# EasyEDA_single_chanel_pump.net
KiCad netlist of a schematic drawn in EasyEDA
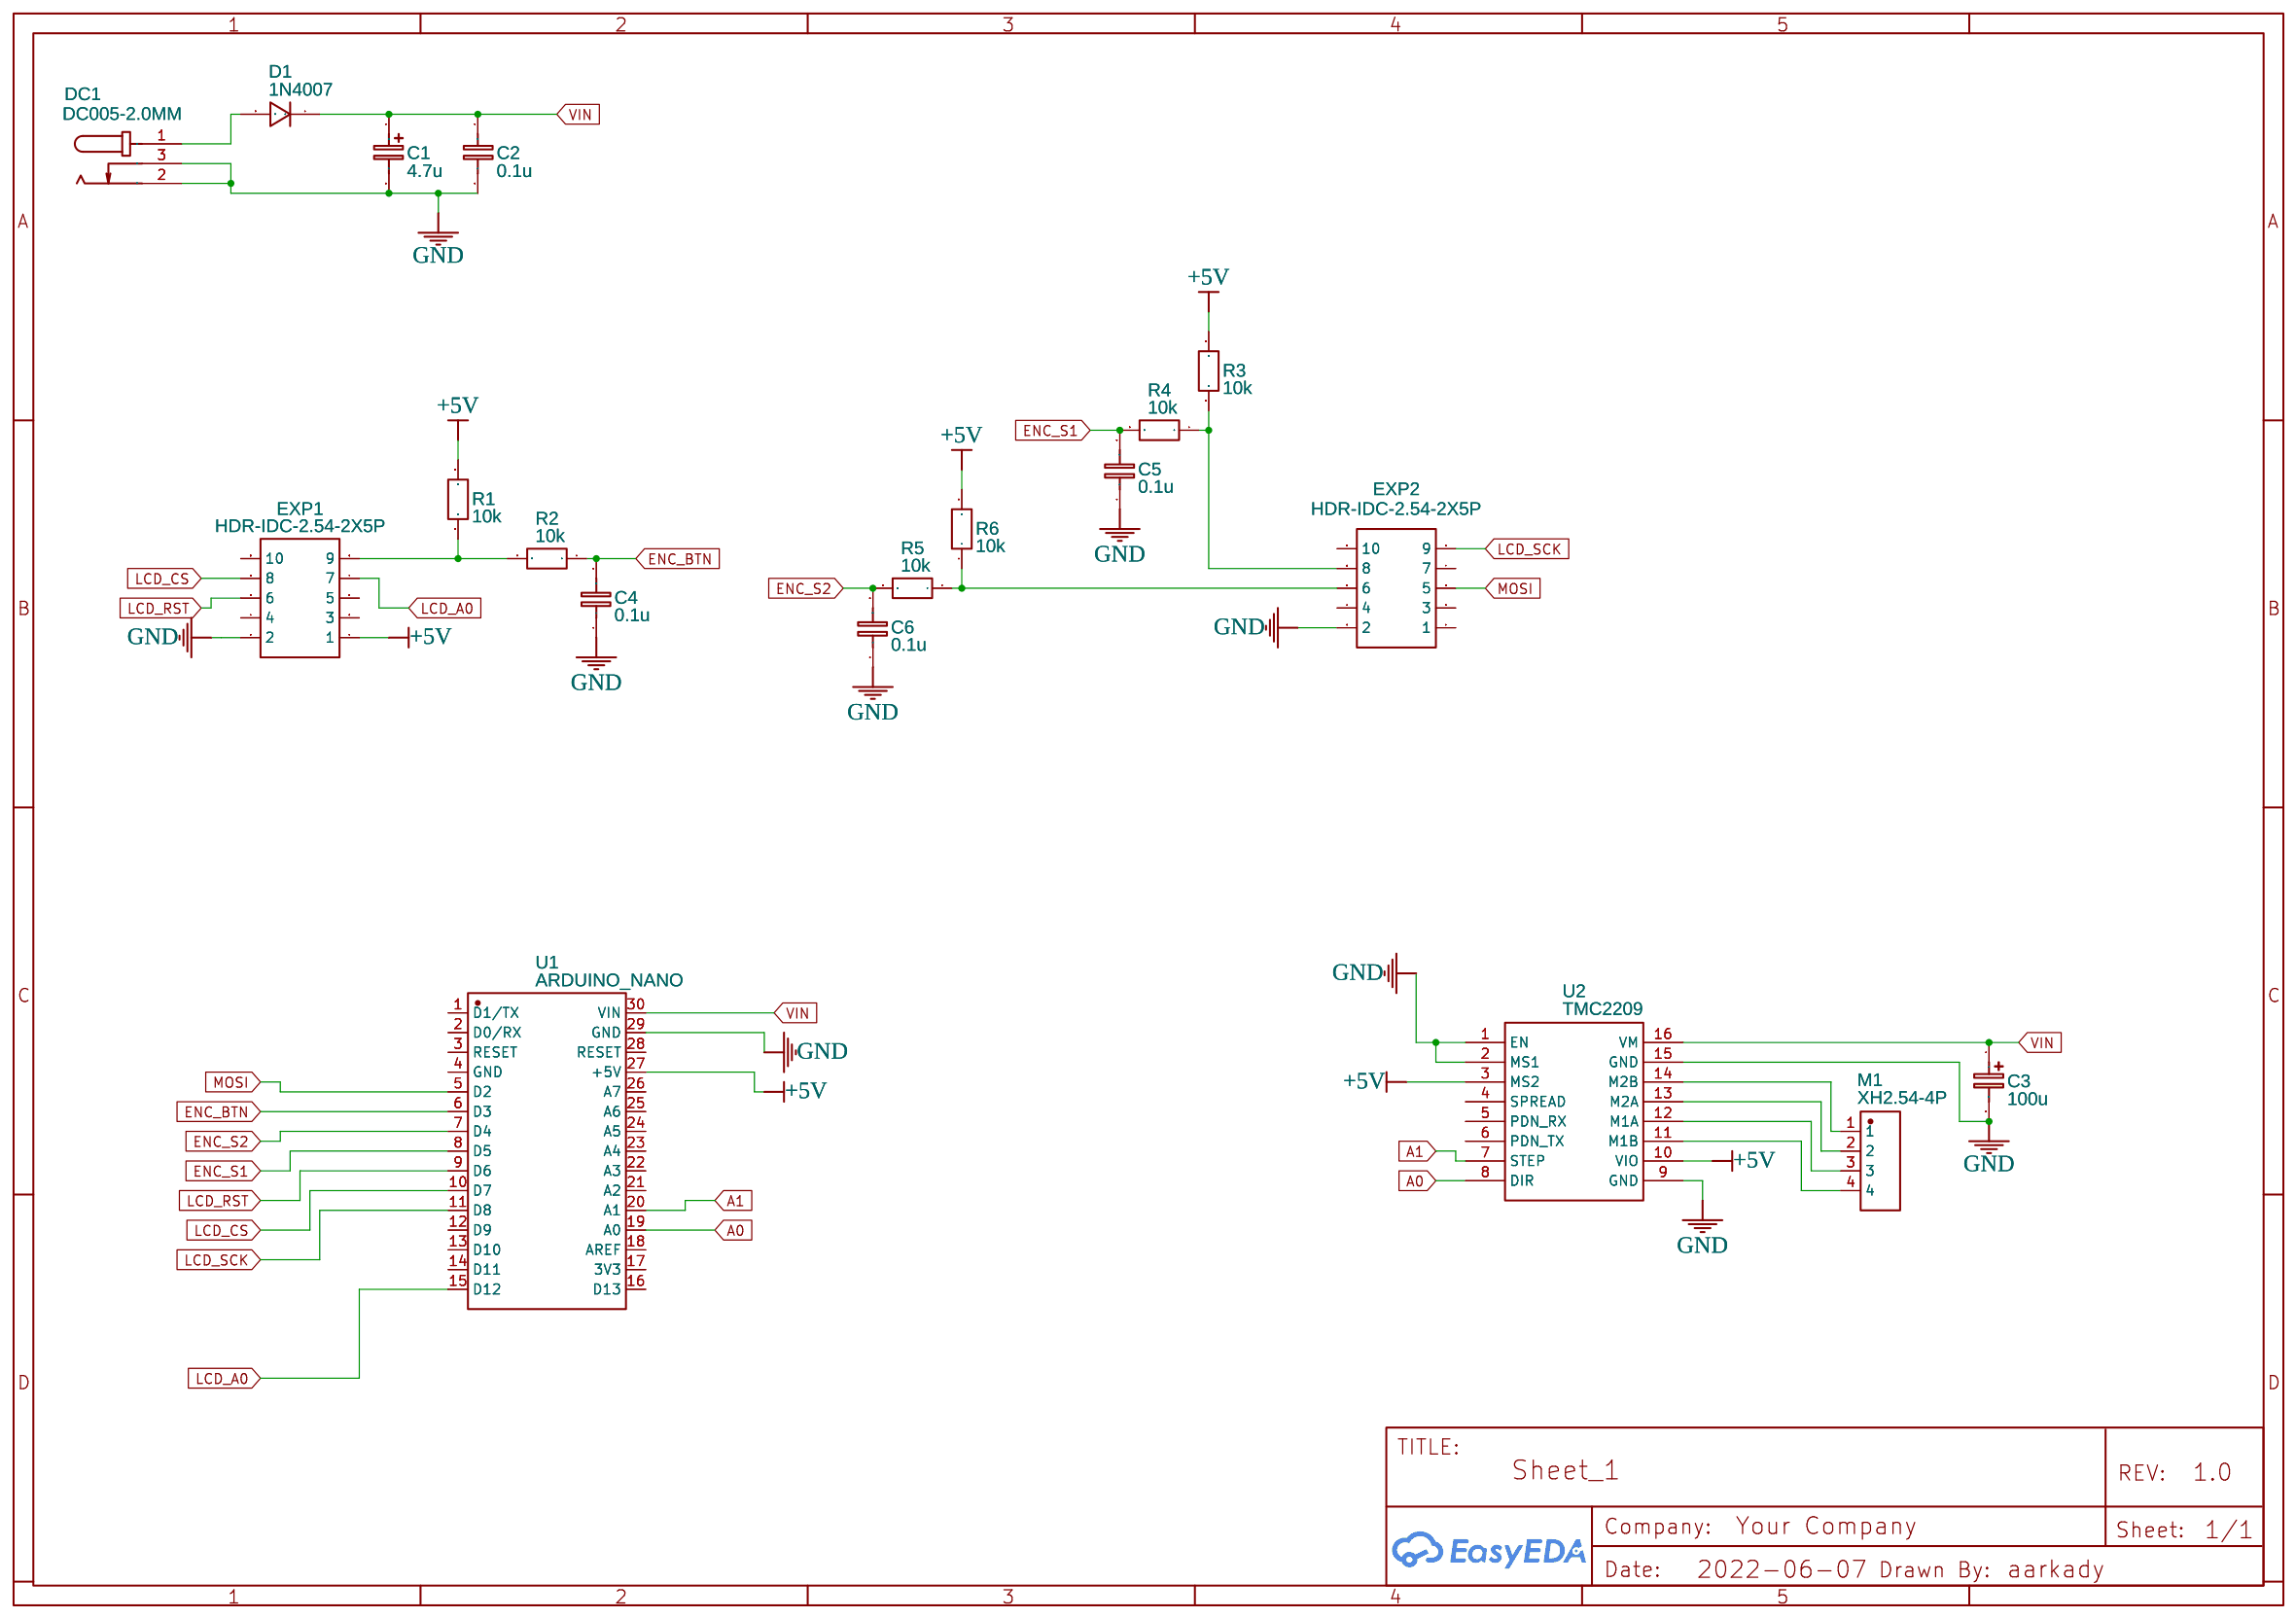
[diagram p0: schematic sheet]

(export (version "E")
  (design (tool "Eeschema 10.0.6"))
  (components
    (comp (ref "C1") (value "4.7u") (libsource (lib "") (part "CE_TH_D5.0×F2.0_EU_1")))
    (comp (ref "C2") (value "0.1u") (libsource (lib "") (part "C_RAD-0.2_EU_2")))
    (comp (ref "C3") (value "100u") (libsource (lib "") (part "CE_TH_D5.0×F2.0_EU")))
    (comp (ref "C4") (value "0.1u") (libsource (lib "") (part "C_RAD-0.2_EU_1")))
    (comp (ref "C5") (value "0.1u") (libsource (lib "") (part "C_RAD-0.2_EU")))
    (comp (ref "C6") (value "0.1u") (libsource (lib "") (part "C_RAD-0.2_EU_3")))
    (comp (ref "D1")
      (value "1N4007")
      (fields (field (name "BOM_Supplier Part") "C106903"))
      (libsource (lib "") (part "1N4007"))
    )
    (comp (ref "DC1")
      (value "DC005-2.0MM")
      (fields (field (name "BOM_Supplier Part") "C111567"))
      (libsource (lib "") (part "DC005-2.0MM"))
    )
    (comp (ref "EXP1")
      (value "HDR-IDC-2.54-2X5P")
      (fields
        (field (name "BOM_Manufacturer Part") "IDC Box 2.54mm 2X5P")
        (field (name "BOM_Supplier Part") "C5665")
      )
      (libsource (lib "") (part "HDR-IDC-2.54-2X5P"))
    )
    (comp (ref "EXP2")
      (value "HDR-IDC-2.54-2X5P")
      (fields
        (field (name "BOM_Manufacturer Part") "IDC Box 2.54mm 2X5P")
        (field (name "BOM_Supplier Part") "C5665")
      )
      (libsource (lib "") (part "HDR-IDC-2.54-2X5P"))
    )
    (comp (ref "M1")
      (value "XH2.54-4P")
      (fields (field (name "BOM_Supplier Part") "C9900003326"))
      (libsource (lib "") (part "XH2.54-4P"))
    )
    (comp (ref "R1") (value "10k") (libsource (lib "") (part "R_AXIAL-0.3_EU_1")))
    (comp (ref "R2") (value "10k") (libsource (lib "") (part "R_AXIAL-0.3_EU")))
    (comp (ref "R3") (value "10k") (libsource (lib "") (part "R_AXIAL-0.3_EU_1")))
    (comp (ref "R4") (value "10k") (libsource (lib "") (part "R_AXIAL-0.3_EU")))
    (comp (ref "R5") (value "10k") (libsource (lib "") (part "R_AXIAL-0.3_EU")))
    (comp (ref "R6") (value "10k") (libsource (lib "") (part "R_AXIAL-0.3_EU_1")))
    (comp (ref "U1")
      (value "ARDUINO_NANO")
      (fields (field (name "BOM_Supplier Part") "C9900017879"))
      (libsource (lib "") (part "ARDUINO_NANO"))
    )
    (comp (ref "U2") (value "TMC2209") (libsource (lib "") (part "TMC2209")))
  )
  (nets
    (net (code "1") (name "+5V") (class "Default")
      (node (ref "EXP1") (pin "1") (pinfunction "1_1") (pintype "unspecified"))
      (node (ref "R1") (pin "2") (pinfunction "2_2") (pintype "unspecified"))
      (node (ref "R3") (pin "2") (pinfunction "2_2") (pintype "unspecified"))
      (node (ref "R6") (pin "2") (pinfunction "2_2") (pintype "unspecified"))
      (node (ref "U1") (pin "27") (pinfunction "+5V_27") (pintype "unspecified"))
      (node (ref "U2") (pin "10") (pinfunction "VIO_10") (pintype "unspecified"))
      (node (ref "U2") (pin "3") (pinfunction "MS2_3") (pintype "unspecified"))
    )
    (net (code "2") (name "A0") (class "Default")
      (node (ref "U1") (pin "19") (pinfunction "A0_19") (pintype "unspecified"))
      (node (ref "U2") (pin "8") (pinfunction "DIR_8") (pintype "unspecified"))
    )
    (net (code "3") (name "A1") (class "Default")
      (node (ref "U1") (pin "20") (pinfunction "A1_20") (pintype "unspecified"))
      (node (ref "U2") (pin "7") (pinfunction "STEP_7") (pintype "unspecified"))
    )
    (net (code "4") (name "ENC_BTN") (class "Default")
      (node (ref "C4") (pin "2") (pinfunction "2_2") (pintype "unspecified"))
      (node (ref "R2") (pin "1") (pinfunction "1_1") (pintype "unspecified"))
      (node (ref "U1") (pin "6") (pinfunction "D3_6") (pintype "unspecified"))
    )
    (net (code "5") (name "ENC_S1") (class "Default")
      (node (ref "C5") (pin "2") (pinfunction "2_2") (pintype "unspecified"))
      (node (ref "R4") (pin "2") (pinfunction "2_2") (pintype "unspecified"))
      (node (ref "U1") (pin "8") (pinfunction "D5_8") (pintype "unspecified"))
    )
    (net (code "6") (name "ENC_S2") (class "Default")
      (node (ref "C6") (pin "2") (pinfunction "2_2") (pintype "unspecified"))
      (node (ref "R5") (pin "2") (pinfunction "2_2") (pintype "unspecified"))
      (node (ref "U1") (pin "7") (pinfunction "D4_7") (pintype "unspecified"))
    )
    (net (code "7") (name "GND") (class "Default")
      (node (ref "C1") (pin "2") (pinfunction "2_2") (pintype "unspecified"))
      (node (ref "C2") (pin "2") (pinfunction "2_2") (pintype "unspecified"))
      (node (ref "C3") (pin "2") (pinfunction "2_2") (pintype "unspecified"))
      (node (ref "C4") (pin "1") (pinfunction "1_1") (pintype "unspecified"))
      (node (ref "C5") (pin "1") (pinfunction "1_1") (pintype "unspecified"))
      (node (ref "C6") (pin "1") (pinfunction "1_1") (pintype "unspecified"))
      (node (ref "DC1") (pin "2") (pinfunction "2_2") (pintype "unspecified"))
      (node (ref "DC1") (pin "3") (pinfunction "3_3") (pintype "unspecified"))
      (node (ref "EXP1") (pin "2") (pinfunction "2_2") (pintype "unspecified"))
      (node (ref "EXP2") (pin "2") (pinfunction "2_2") (pintype "unspecified"))
      (node (ref "U1") (pin "29") (pinfunction "GND_29") (pintype "unspecified"))
      (node (ref "U2") (pin "1") (pinfunction "EN_1") (pintype "unspecified"))
      (node (ref "U2") (pin "15") (pinfunction "GND_15") (pintype "unspecified"))
      (node (ref "U2") (pin "2") (pinfunction "MS1_2") (pintype "unspecified"))
      (node (ref "U2") (pin "9") (pinfunction "GND_9") (pintype "unspecified"))
    )
    (net (code "8") (name "LCD_A0") (class "Default")
      (node (ref "EXP1") (pin "7") (pinfunction "7_7") (pintype "unspecified"))
      (node (ref "U1") (pin "15") (pinfunction "D12_15") (pintype "unspecified"))
    )
    (net (code "9") (name "LCD_CS") (class "Default")
      (node (ref "EXP1") (pin "8") (pinfunction "8_8") (pintype "unspecified"))
      (node (ref "U1") (pin "10") (pinfunction "D7_10") (pintype "unspecified"))
    )
    (net (code "10") (name "LCD_RST") (class "Default")
      (node (ref "EXP1") (pin "6") (pinfunction "6_6") (pintype "unspecified"))
      (node (ref "U1") (pin "9") (pinfunction "D6_9") (pintype "unspecified"))
    )
    (net (code "11") (name "LCD_SCK") (class "Default")
      (node (ref "EXP2") (pin "9") (pinfunction "9_9") (pintype "unspecified"))
      (node (ref "U1") (pin "11") (pinfunction "D8_11") (pintype "unspecified"))
    )
    (net (code "12") (name "MOSI") (class "Default")
      (node (ref "EXP2") (pin "5") (pinfunction "5_5") (pintype "unspecified"))
      (node (ref "U1") (pin "5") (pinfunction "D2_5") (pintype "unspecified"))
    )
    (net (code "13") (name "Net-(D1-Pad2)") (class "Default")
      (node (ref "D1") (pin "2") (pinfunction "2_2") (pintype "unspecified"))
      (node (ref "DC1") (pin "1") (pinfunction "1_1") (pintype "unspecified"))
    )
    (net (code "14") (name "Net-(EXP1-Pad9)") (class "Default")
      (node (ref "EXP1") (pin "9") (pinfunction "9_9") (pintype "unspecified"))
      (node (ref "R1") (pin "1") (pinfunction "1_1") (pintype "unspecified"))
      (node (ref "R2") (pin "2") (pinfunction "2_2") (pintype "unspecified"))
    )
    (net (code "15") (name "Net-(EXP2-Pad6)") (class "Default")
      (node (ref "EXP2") (pin "6") (pinfunction "6_6") (pintype "unspecified"))
      (node (ref "R5") (pin "1") (pinfunction "1_1") (pintype "unspecified"))
      (node (ref "R6") (pin "1") (pinfunction "1_1") (pintype "unspecified"))
    )
    (net (code "16") (name "Net-(EXP2-Pad8)") (class "Default")
      (node (ref "EXP2") (pin "8") (pinfunction "8_8") (pintype "unspecified"))
      (node (ref "R3") (pin "1") (pinfunction "1_1") (pintype "unspecified"))
      (node (ref "R4") (pin "1") (pinfunction "1_1") (pintype "unspecified"))
    )
    (net (code "17") (name "Net-(U2-M1A)") (class "Default")
      (node (ref "M1") (pin "3") (pinfunction "3_3") (pintype "unspecified"))
      (node (ref "U2") (pin "12") (pinfunction "M1A_12") (pintype "unspecified"))
    )
    (net (code "18") (name "Net-(U2-M1B)") (class "Default")
      (node (ref "M1") (pin "4") (pinfunction "4_4") (pintype "unspecified"))
      (node (ref "U2") (pin "11") (pinfunction "M1B_11") (pintype "unspecified"))
    )
    (net (code "19") (name "Net-(U2-M2A)") (class "Default")
      (node (ref "M1") (pin "2") (pinfunction "2_2") (pintype "unspecified"))
      (node (ref "U2") (pin "13") (pinfunction "M2A_13") (pintype "unspecified"))
    )
    (net (code "20") (name "Net-(U2-M2B)") (class "Default")
      (node (ref "M1") (pin "1") (pinfunction "1_1") (pintype "unspecified"))
      (node (ref "U2") (pin "14") (pinfunction "M2B_14") (pintype "unspecified"))
    )
    (net (code "21") (name "VIN") (class "Default")
      (node (ref "C1") (pin "1") (pinfunction "1_1") (pintype "unspecified"))
      (node (ref "C2") (pin "1") (pinfunction "1_1") (pintype "unspecified"))
      (node (ref "C3") (pin "1") (pinfunction "1_1") (pintype "unspecified"))
      (node (ref "D1") (pin "1") (pinfunction "1_1") (pintype "unspecified"))
      (node (ref "U1") (pin "30") (pinfunction "VIN_30") (pintype "unspecified"))
      (node (ref "U2") (pin "16") (pinfunction "VM_16") (pintype "unspecified"))
    )
    (net (code "22") (name "unconnected-(EXP1-Pad3)") (class "Default")
      (node (ref "EXP1") (pin "3") (pinfunction "3_3") (pintype "unspecified"))
    )
    (net (code "23") (name "unconnected-(EXP1-Pad4)") (class "Default")
      (node (ref "EXP1") (pin "4") (pinfunction "4_4") (pintype "unspecified"))
    )
    (net (code "24") (name "unconnected-(EXP1-Pad5)") (class "Default")
      (node (ref "EXP1") (pin "5") (pinfunction "5_5") (pintype "unspecified"))
    )
    (net (code "25") (name "unconnected-(EXP1-Pad10)") (class "Default")
      (node (ref "EXP1") (pin "10") (pinfunction "10_10") (pintype "unspecified"))
    )
    (net (code "26") (name "unconnected-(EXP2-Pad1)") (class "Default")
      (node (ref "EXP2") (pin "1") (pinfunction "1_1") (pintype "unspecified"))
    )
    (net (code "27") (name "unconnected-(EXP2-Pad3)") (class "Default")
      (node (ref "EXP2") (pin "3") (pinfunction "3_3") (pintype "unspecified"))
    )
    (net (code "28") (name "unconnected-(EXP2-Pad4)") (class "Default")
      (node (ref "EXP2") (pin "4") (pinfunction "4_4") (pintype "unspecified"))
    )
    (net (code "29") (name "unconnected-(EXP2-Pad7)") (class "Default")
      (node (ref "EXP2") (pin "7") (pinfunction "7_7") (pintype "unspecified"))
    )
    (net (code "30") (name "unconnected-(EXP2-Pad10)") (class "Default")
      (node (ref "EXP2") (pin "10") (pinfunction "10_10") (pintype "unspecified"))
    )
    (net (code "31") (name "unconnected-(U1-3V3-Pad17)") (class "Default")
      (node (ref "U1") (pin "17") (pinfunction "3V3_17") (pintype "unspecified"))
    )
    (net (code "32") (name "unconnected-(U1-A2-Pad21)") (class "Default")
      (node (ref "U1") (pin "21") (pinfunction "A2_21") (pintype "unspecified"))
    )
    (net (code "33") (name "unconnected-(U1-A3-Pad22)") (class "Default")
      (node (ref "U1") (pin "22") (pinfunction "A3_22") (pintype "unspecified"))
    )
    (net (code "34") (name "unconnected-(U1-A4-Pad23)") (class "Default")
      (node (ref "U1") (pin "23") (pinfunction "A4_23") (pintype "unspecified"))
    )
    (net (code "35") (name "unconnected-(U1-A5-Pad24)") (class "Default")
      (node (ref "U1") (pin "24") (pinfunction "A5_24") (pintype "unspecified"))
    )
    (net (code "36") (name "unconnected-(U1-A6-Pad25)") (class "Default")
      (node (ref "U1") (pin "25") (pinfunction "A6_25") (pintype "unspecified"))
    )
    (net (code "37") (name "unconnected-(U1-A7-Pad26)") (class "Default")
      (node (ref "U1") (pin "26") (pinfunction "A7_26") (pintype "unspecified"))
    )
    (net (code "38") (name "unconnected-(U1-AREF-Pad18)") (class "Default")
      (node (ref "U1") (pin "18") (pinfunction "AREF_18") (pintype "unspecified"))
    )
    (net (code "39") (name "unconnected-(U1-D0{slash}RX-Pad2)") (class "Default")
      (node (ref "U1") (pin "2") (pinfunction "D0/RX_2") (pintype "unspecified"))
    )
    (net (code "40") (name "unconnected-(U1-D1{slash}TX-Pad1)") (class "Default")
      (node (ref "U1") (pin "1") (pinfunction "D1/TX_1") (pintype "unspecified"))
    )
    (net (code "41") (name "unconnected-(U1-D9-Pad12)") (class "Default")
      (node (ref "U1") (pin "12") (pinfunction "D9_12") (pintype "unspecified"))
    )
    (net (code "42") (name "unconnected-(U1-D10-Pad13)") (class "Default")
      (node (ref "U1") (pin "13") (pinfunction "D10_13") (pintype "unspecified"))
    )
    (net (code "43") (name "unconnected-(U1-D11-Pad14)") (class "Default")
      (node (ref "U1") (pin "14") (pinfunction "D11_14") (pintype "unspecified"))
    )
    (net (code "44") (name "unconnected-(U1-D13-Pad16)") (class "Default")
      (node (ref "U1") (pin "16") (pinfunction "D13_16") (pintype "unspecified"))
    )
    (net (code "45") (name "unconnected-(U1-GND-Pad4)") (class "Default")
      (node (ref "U1") (pin "4") (pinfunction "GND_4") (pintype "unspecified"))
    )
    (net (code "46") (name "unconnected-(U1-RESET-Pad3)") (class "Default")
      (node (ref "U1") (pin "3") (pinfunction "RESET_3") (pintype "unspecified"))
    )
    (net (code "47") (name "unconnected-(U1-RESET-Pad28)") (class "Default")
      (node (ref "U1") (pin "28") (pinfunction "RESET_28") (pintype "unspecified"))
    )
    (net (code "48") (name "unconnected-(U2-PDN_RX-Pad5)") (class "Default")
      (node (ref "U2") (pin "5") (pinfunction "PDN_RX_5") (pintype "unspecified"))
    )
    (net (code "49") (name "unconnected-(U2-PDN_TX-Pad6)") (class "Default")
      (node (ref "U2") (pin "6") (pinfunction "PDN_TX_6") (pintype "unspecified"))
    )
    (net (code "50") (name "unconnected-(U2-SPREAD-Pad4)") (class "Default")
      (node (ref "U2") (pin "4") (pinfunction "SPREAD_4") (pintype "unspecified"))
    )
  )
)
